# SprinklerPi.net
KiCad netlist of a schematic drawn in EAGLE
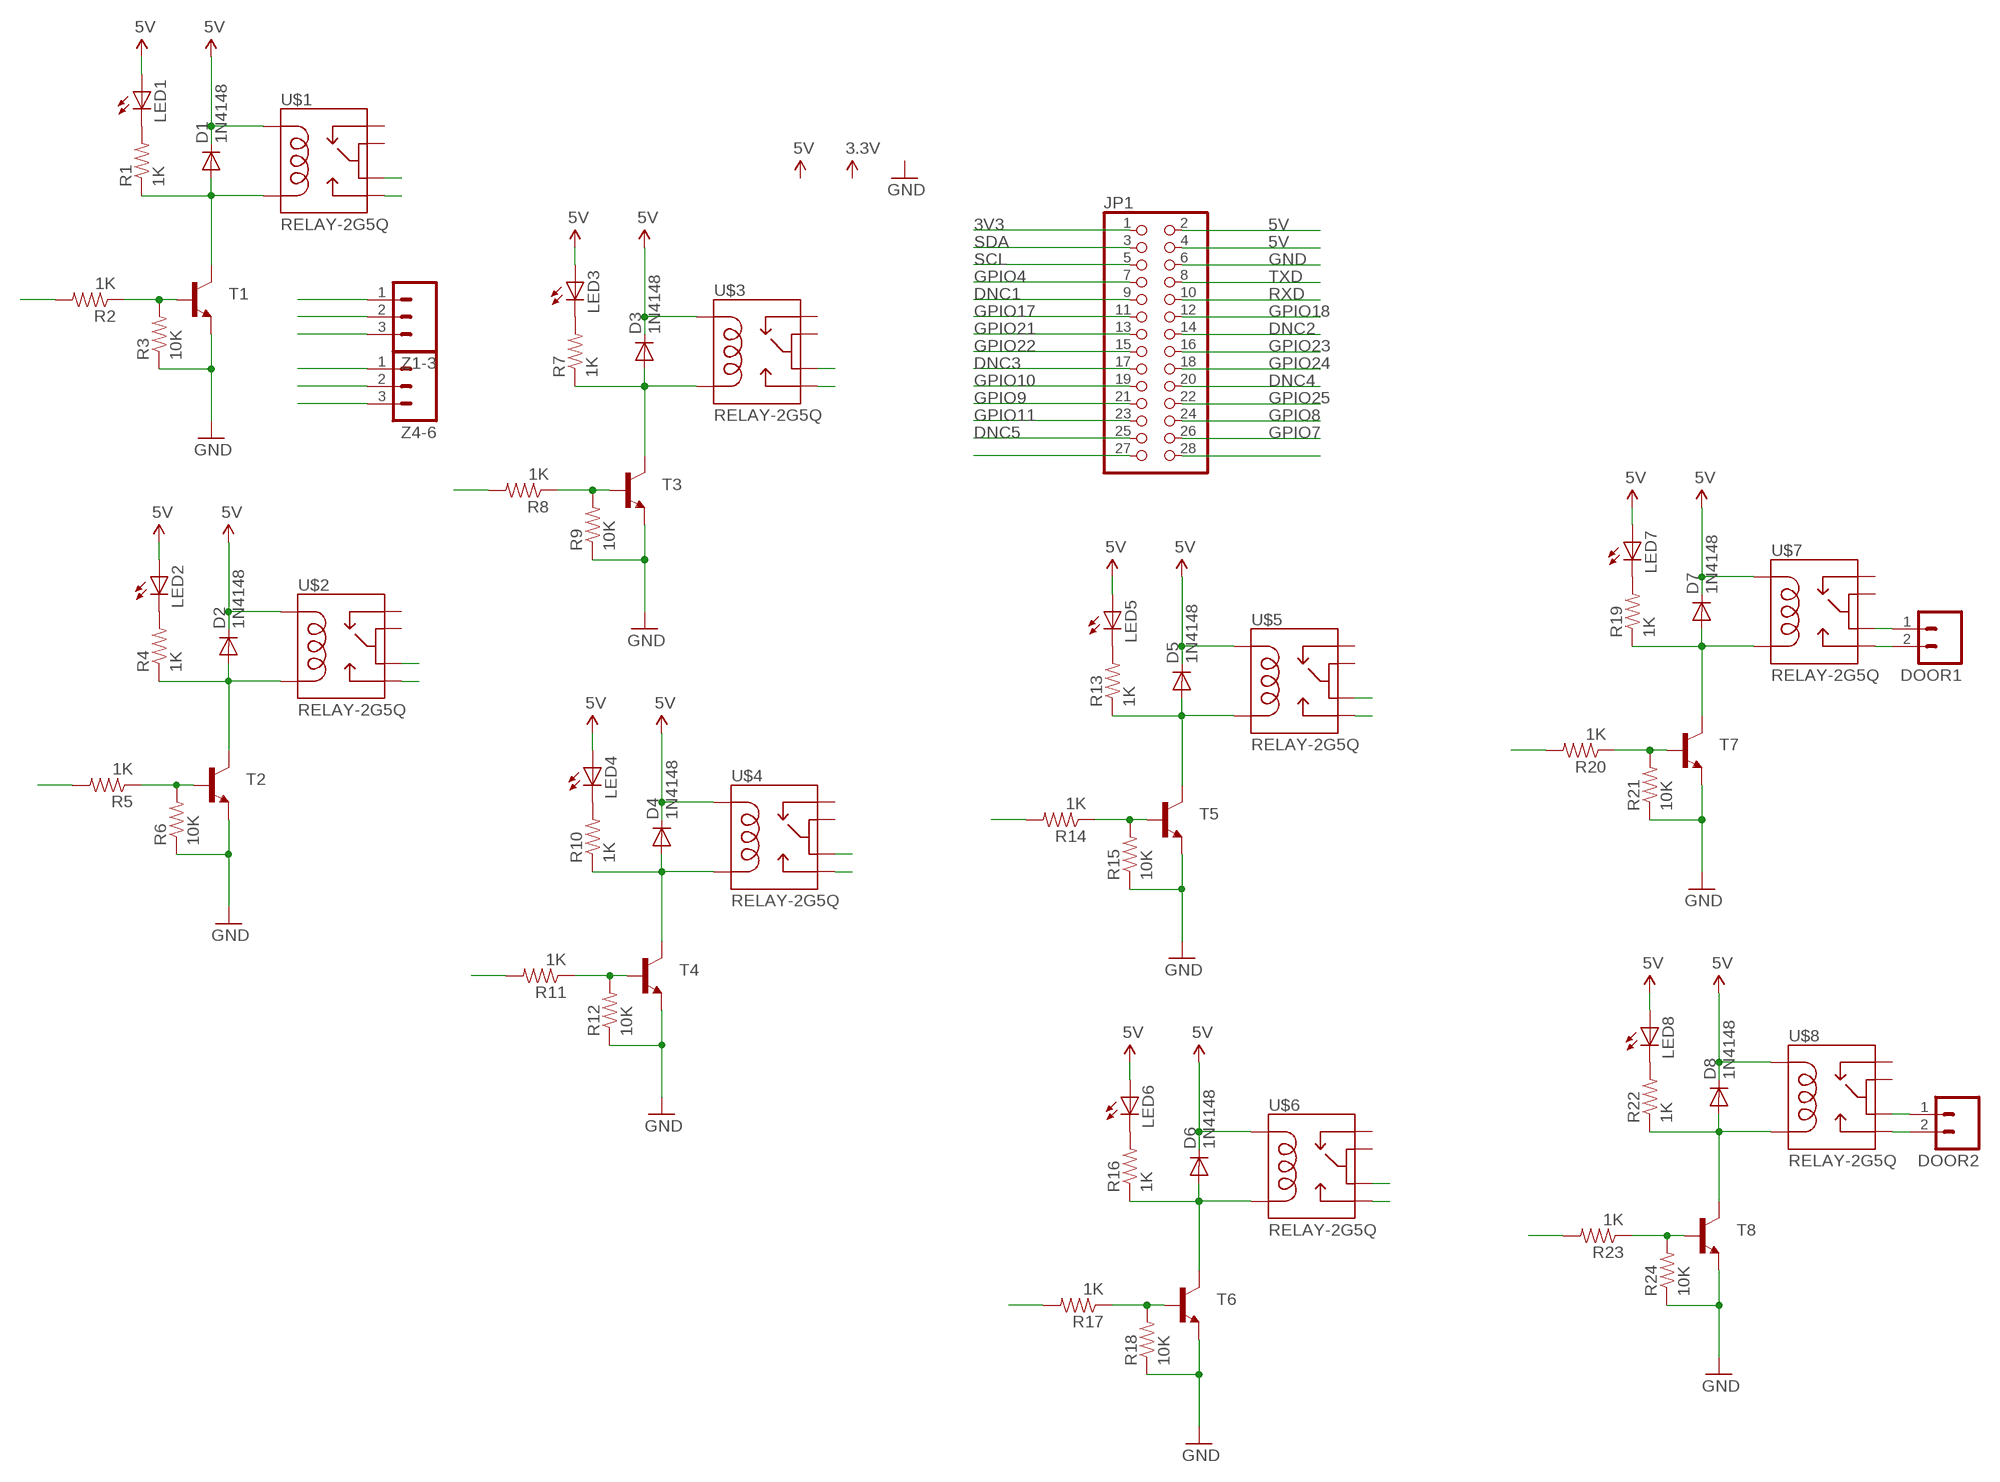
[diagram p0: schematic, sheet 1]

(export (version "E")
  (design (tool "Eeschema 10.0.6"))
  (components
    (comp (ref "D1")
      (value "1N4148")
      (footprint "eagle-import:DIODE-1N4148")
      (libsource (lib "eagle-import") (part "DIODE1N4148"))
    )
    (comp (ref "D2")
      (value "1N4148")
      (footprint "eagle-import:DIODE-1N4148")
      (libsource (lib "eagle-import") (part "DIODE1N4148"))
    )
    (comp (ref "D3")
      (value "1N4148")
      (footprint "eagle-import:DIODE-1N4148")
      (libsource (lib "eagle-import") (part "DIODE1N4148"))
    )
    (comp (ref "D4")
      (value "1N4148")
      (footprint "eagle-import:DIODE-1N4148")
      (libsource (lib "eagle-import") (part "DIODE1N4148"))
    )
    (comp (ref "D5")
      (value "1N4148")
      (footprint "eagle-import:DIODE-1N4148")
      (libsource (lib "eagle-import") (part "DIODE1N4148"))
    )
    (comp (ref "D6")
      (value "1N4148")
      (footprint "eagle-import:DIODE-1N4148")
      (libsource (lib "eagle-import") (part "DIODE1N4148"))
    )
    (comp (ref "D7")
      (value "1N4148")
      (footprint "eagle-import:DIODE-1N4148")
      (libsource (lib "eagle-import") (part "DIODE1N4148"))
    )
    (comp (ref "D8")
      (value "1N4148")
      (footprint "eagle-import:DIODE-1N4148")
      (libsource (lib "eagle-import") (part "DIODE1N4148"))
    )
    (comp (ref "DOOR1")
      (value "M023.5MM")
      (footprint "eagle-import:SCREWTERMINAL-3.5MM-2")
      (libsource (lib "eagle-import") (part "M023.5MM"))
    )
    (comp (ref "DOOR2")
      (value "M023.5MM")
      (footprint "eagle-import:SCREWTERMINAL-3.5MM-2")
      (libsource (lib "eagle-import") (part "M023.5MM"))
    )
    (comp (ref "JP1")
      (value "PINHD-2X14-CB")
      (footprint "eagle-import:2X14-CLEANBIG")
      (libsource (lib "eagle-import") (part "PINHD-2X14-CB"))
    )
    (comp (ref "LED1")
      (value "LED-RED1206")
      (footprint "eagle-import:LED-1206")
      (libsource (lib "eagle-import") (part "LED-RED1206"))
    )
    (comp (ref "LED2")
      (value "LED-RED1206")
      (footprint "eagle-import:LED-1206")
      (libsource (lib "eagle-import") (part "LED-RED1206"))
    )
    (comp (ref "LED3")
      (value "LED-RED1206")
      (footprint "eagle-import:LED-1206")
      (libsource (lib "eagle-import") (part "LED-RED1206"))
    )
    (comp (ref "LED4")
      (value "LED-RED1206")
      (footprint "eagle-import:LED-1206")
      (libsource (lib "eagle-import") (part "LED-RED1206"))
    )
    (comp (ref "LED5")
      (value "LED-RED1206")
      (footprint "eagle-import:LED-1206")
      (libsource (lib "eagle-import") (part "LED-RED1206"))
    )
    (comp (ref "LED6")
      (value "LED-RED1206")
      (footprint "eagle-import:LED-1206")
      (libsource (lib "eagle-import") (part "LED-RED1206"))
    )
    (comp (ref "LED7")
      (value "LED-RED1206")
      (footprint "eagle-import:LED-1206")
      (libsource (lib "eagle-import") (part "LED-RED1206"))
    )
    (comp (ref "LED8")
      (value "LED-RED1206")
      (footprint "eagle-import:LED-1206")
      (libsource (lib "eagle-import") (part "LED-RED1206"))
    )
    (comp (ref "R1")
      (value "1K")
      (footprint "eagle-import:0805")
      (libsource (lib "eagle-import") (part "RESISTOR0805-RES"))
    )
    (comp (ref "R2")
      (value "1K")
      (footprint "eagle-import:0805")
      (libsource (lib "eagle-import") (part "RESISTOR0805-RES"))
    )
    (comp (ref "R3")
      (value "10K")
      (footprint "eagle-import:0805")
      (libsource (lib "eagle-import") (part "RESISTOR0805-RES"))
    )
    (comp (ref "R4")
      (value "1K")
      (footprint "eagle-import:0805")
      (libsource (lib "eagle-import") (part "RESISTOR0805-RES"))
    )
    (comp (ref "R5")
      (value "1K")
      (footprint "eagle-import:0805")
      (libsource (lib "eagle-import") (part "RESISTOR0805-RES"))
    )
    (comp (ref "R6")
      (value "10K")
      (footprint "eagle-import:0805")
      (libsource (lib "eagle-import") (part "RESISTOR0805-RES"))
    )
    (comp (ref "R7")
      (value "1K")
      (footprint "eagle-import:0805")
      (libsource (lib "eagle-import") (part "RESISTOR0805-RES"))
    )
    (comp (ref "R8")
      (value "1K")
      (footprint "eagle-import:0805")
      (libsource (lib "eagle-import") (part "RESISTOR0805-RES"))
    )
    (comp (ref "R9")
      (value "10K")
      (footprint "eagle-import:0805")
      (libsource (lib "eagle-import") (part "RESISTOR0805-RES"))
    )
    (comp (ref "R10")
      (value "1K")
      (footprint "eagle-import:0805")
      (libsource (lib "eagle-import") (part "RESISTOR0805-RES"))
    )
    (comp (ref "R11")
      (value "1K")
      (footprint "eagle-import:0805")
      (libsource (lib "eagle-import") (part "RESISTOR0805-RES"))
    )
    (comp (ref "R12")
      (value "10K")
      (footprint "eagle-import:0805")
      (libsource (lib "eagle-import") (part "RESISTOR0805-RES"))
    )
    (comp (ref "R13")
      (value "1K")
      (footprint "eagle-import:0805")
      (libsource (lib "eagle-import") (part "RESISTOR0805-RES"))
    )
    (comp (ref "R14")
      (value "1K")
      (footprint "eagle-import:0805")
      (libsource (lib "eagle-import") (part "RESISTOR0805-RES"))
    )
    (comp (ref "R15")
      (value "10K")
      (footprint "eagle-import:0805")
      (libsource (lib "eagle-import") (part "RESISTOR0805-RES"))
    )
    (comp (ref "R16")
      (value "1K")
      (footprint "eagle-import:0805")
      (libsource (lib "eagle-import") (part "RESISTOR0805-RES"))
    )
    (comp (ref "R17")
      (value "1K")
      (footprint "eagle-import:0805")
      (libsource (lib "eagle-import") (part "RESISTOR0805-RES"))
    )
    (comp (ref "R18")
      (value "10K")
      (footprint "eagle-import:0805")
      (libsource (lib "eagle-import") (part "RESISTOR0805-RES"))
    )
    (comp (ref "R19")
      (value "1K")
      (footprint "eagle-import:0805")
      (libsource (lib "eagle-import") (part "RESISTOR0805-RES"))
    )
    (comp (ref "R20")
      (value "1K")
      (footprint "eagle-import:0805")
      (libsource (lib "eagle-import") (part "RESISTOR0805-RES"))
    )
    (comp (ref "R21")
      (value "10K")
      (footprint "eagle-import:0805")
      (libsource (lib "eagle-import") (part "RESISTOR0805-RES"))
    )
    (comp (ref "R22")
      (value "1K")
      (footprint "eagle-import:0805")
      (libsource (lib "eagle-import") (part "RESISTOR0805-RES"))
    )
    (comp (ref "R23")
      (value "1K")
      (footprint "eagle-import:0805")
      (libsource (lib "eagle-import") (part "RESISTOR0805-RES"))
    )
    (comp (ref "R24")
      (value "10K")
      (footprint "eagle-import:0805")
      (libsource (lib "eagle-import") (part "RESISTOR0805-RES"))
    )
    (comp (ref "T1")
      (value "TRANSISTOR_NPNSOT23")
      (footprint "eagle-import:SOT23")
      (libsource (lib "eagle-import") (part "TRANSISTOR_NPNSOT23"))
    )
    (comp (ref "T2")
      (value "TRANSISTOR_NPNSOT23")
      (footprint "eagle-import:SOT23")
      (libsource (lib "eagle-import") (part "TRANSISTOR_NPNSOT23"))
    )
    (comp (ref "T3")
      (value "TRANSISTOR_NPNSOT23")
      (footprint "eagle-import:SOT23")
      (libsource (lib "eagle-import") (part "TRANSISTOR_NPNSOT23"))
    )
    (comp (ref "T4")
      (value "TRANSISTOR_NPNSOT23")
      (footprint "eagle-import:SOT23")
      (libsource (lib "eagle-import") (part "TRANSISTOR_NPNSOT23"))
    )
    (comp (ref "T5")
      (value "TRANSISTOR_NPNSOT23")
      (footprint "eagle-import:SOT23")
      (libsource (lib "eagle-import") (part "TRANSISTOR_NPNSOT23"))
    )
    (comp (ref "T6")
      (value "TRANSISTOR_NPNSOT23")
      (footprint "eagle-import:SOT23")
      (libsource (lib "eagle-import") (part "TRANSISTOR_NPNSOT23"))
    )
    (comp (ref "T7")
      (value "TRANSISTOR_NPNSOT23")
      (footprint "eagle-import:SOT23")
      (libsource (lib "eagle-import") (part "TRANSISTOR_NPNSOT23"))
    )
    (comp (ref "T8")
      (value "TRANSISTOR_NPNSOT23")
      (footprint "eagle-import:SOT23")
      (libsource (lib "eagle-import") (part "TRANSISTOR_NPNSOT23"))
    )
    (comp (ref "U$1")
      (value "RELAY-2G5Q")
      (footprint "eagle-import:RELAY-G5V")
      (libsource (lib "eagle-import") (part "RELAY-2G5Q"))
    )
    (comp (ref "U$2")
      (value "RELAY-2G5Q")
      (footprint "eagle-import:RELAY-G5V")
      (libsource (lib "eagle-import") (part "RELAY-2G5Q"))
    )
    (comp (ref "U$3")
      (value "RELAY-2G5Q")
      (footprint "eagle-import:RELAY-G5V")
      (libsource (lib "eagle-import") (part "RELAY-2G5Q"))
    )
    (comp (ref "U$4")
      (value "RELAY-2G5Q")
      (footprint "eagle-import:RELAY-G5V")
      (libsource (lib "eagle-import") (part "RELAY-2G5Q"))
    )
    (comp (ref "U$5")
      (value "RELAY-2G5Q")
      (footprint "eagle-import:RELAY-G5V")
      (libsource (lib "eagle-import") (part "RELAY-2G5Q"))
    )
    (comp (ref "U$6")
      (value "RELAY-2G5Q")
      (footprint "eagle-import:RELAY-G5V")
      (libsource (lib "eagle-import") (part "RELAY-2G5Q"))
    )
    (comp (ref "U$7")
      (value "RELAY-2G5Q")
      (footprint "eagle-import:RELAY-G5V")
      (libsource (lib "eagle-import") (part "RELAY-2G5Q"))
    )
    (comp (ref "U$8")
      (value "RELAY-2G5Q")
      (footprint "eagle-import:RELAY-G5V")
      (libsource (lib "eagle-import") (part "RELAY-2G5Q"))
    )
    (comp (ref "Z1-3")
      (value "M03SCREW")
      (footprint "eagle-import:SCREWTERMINAL-3.5MM-3")
      (libsource (lib "eagle-import") (part "M03SCREW"))
    )
    (comp (ref "Z4-6")
      (value "M03SCREW")
      (footprint "eagle-import:SCREWTERMINAL-3.5MM-3")
      (libsource (lib "eagle-import") (part "M03SCREW"))
    )
  )
  (nets
    (net (code "1") (name "/3V3") (class "Default")
      (node (ref "JP1") (pin "1") (pinfunction "1_1") (pintype "passive"))
    )
    (net (code "2") (name "/DNC1") (class "Default")
      (node (ref "JP1") (pin "9") (pinfunction "9_9") (pintype "passive"))
    )
    (net (code "3") (name "/DNC2") (class "Default")
      (node (ref "JP1") (pin "14") (pinfunction "14_14") (pintype "passive"))
    )
    (net (code "4") (name "/DNC3") (class "Default")
      (node (ref "JP1") (pin "17") (pinfunction "17_17") (pintype "passive"))
    )
    (net (code "5") (name "/DNC4") (class "Default")
      (node (ref "JP1") (pin "20") (pinfunction "20_20") (pintype "passive"))
    )
    (net (code "6") (name "/DNC5") (class "Default")
      (node (ref "JP1") (pin "25") (pinfunction "25_25") (pintype "passive"))
    )
    (net (code "7") (name "/GPIO4") (class "Default")
      (node (ref "JP1") (pin "7") (pinfunction "7_7") (pintype "passive"))
    )
    (net (code "8") (name "/GPIO7") (class "Default")
      (node (ref "JP1") (pin "26") (pinfunction "26_26") (pintype "passive"))
    )
    (net (code "9") (name "/GPIO8") (class "Default")
      (node (ref "JP1") (pin "24") (pinfunction "24_24") (pintype "passive"))
    )
    (net (code "10") (name "/GPIO9") (class "Default")
      (node (ref "JP1") (pin "21") (pinfunction "21_21") (pintype "passive"))
    )
    (net (code "11") (name "/GPIO10") (class "Default")
      (node (ref "JP1") (pin "19") (pinfunction "19_19") (pintype "passive"))
    )
    (net (code "12") (name "/GPIO11") (class "Default")
      (node (ref "JP1") (pin "23") (pinfunction "23_23") (pintype "passive"))
    )
    (net (code "13") (name "/GPIO17") (class "Default")
      (node (ref "JP1") (pin "11") (pinfunction "11_11") (pintype "passive"))
    )
    (net (code "14") (name "/GPIO18") (class "Default")
      (node (ref "JP1") (pin "12") (pinfunction "12_12") (pintype "passive"))
    )
    (net (code "15") (name "/GPIO21") (class "Default")
      (node (ref "JP1") (pin "13") (pinfunction "13_13") (pintype "passive"))
    )
    (net (code "16") (name "/GPIO22") (class "Default")
      (node (ref "JP1") (pin "15") (pinfunction "15_15") (pintype "passive"))
    )
    (net (code "17") (name "/GPIO23") (class "Default")
      (node (ref "JP1") (pin "16") (pinfunction "16_16") (pintype "passive"))
    )
    (net (code "18") (name "/GPIO24") (class "Default")
      (node (ref "JP1") (pin "18") (pinfunction "18_18") (pintype "passive"))
    )
    (net (code "19") (name "/GPIO25") (class "Default")
      (node (ref "JP1") (pin "22") (pinfunction "22_22") (pintype "passive"))
    )
    (net (code "20") (name "/RXD") (class "Default")
      (node (ref "JP1") (pin "10") (pinfunction "10_10") (pintype "passive"))
    )
    (net (code "21") (name "/SCL") (class "Default")
      (node (ref "JP1") (pin "5") (pinfunction "5_5") (pintype "passive"))
    )
    (net (code "22") (name "/SDA") (class "Default")
      (node (ref "JP1") (pin "3") (pinfunction "3_3") (pintype "passive"))
    )
    (net (code "23") (name "/TXD") (class "Default")
      (node (ref "JP1") (pin "8") (pinfunction "8_8") (pintype "passive"))
    )
    (net (code "24") (name "/Z1") (class "Default")
      (node (ref "U$1") (pin "10") (pinfunction "10_10") (pintype "bidirectional"))
      (node (ref "Z1-3") (pin "1") (pinfunction "1_1") (pintype "passive"))
    )
    (net (code "25") (name "/Z2") (class "Default")
      (node (ref "U$2") (pin "10") (pinfunction "10_10") (pintype "bidirectional"))
      (node (ref "Z1-3") (pin "2") (pinfunction "2_2") (pintype "passive"))
    )
    (net (code "26") (name "/Z3") (class "Default")
      (node (ref "U$3") (pin "10") (pinfunction "10_10") (pintype "bidirectional"))
      (node (ref "Z1-3") (pin "3") (pinfunction "3_3") (pintype "passive"))
    )
    (net (code "27") (name "/Z4") (class "Default")
      (node (ref "U$4") (pin "10") (pinfunction "10_10") (pintype "bidirectional"))
      (node (ref "Z4-6") (pin "1") (pinfunction "1_1") (pintype "passive"))
    )
    (net (code "28") (name "/Z5") (class "Default")
      (node (ref "U$5") (pin "10") (pinfunction "10_10") (pintype "bidirectional"))
      (node (ref "Z4-6") (pin "2") (pinfunction "2_2") (pintype "passive"))
    )
    (net (code "29") (name "/Z6") (class "Default")
      (node (ref "U$6") (pin "10") (pinfunction "10_10") (pintype "bidirectional"))
      (node (ref "Z4-6") (pin "3") (pinfunction "3_3") (pintype "passive"))
    )
    (net (code "31") (name "5V") (class "Default")
      (node (ref "D1") (pin "C") (pinfunction "C_C") (pintype "passive"))
      (node (ref "D2") (pin "C") (pinfunction "C_C") (pintype "passive"))
      (node (ref "D3") (pin "C") (pinfunction "C_C") (pintype "passive"))
      (node (ref "D4") (pin "C") (pinfunction "C_C") (pintype "passive"))
      (node (ref "D5") (pin "C") (pinfunction "C_C") (pintype "passive"))
      (node (ref "D6") (pin "C") (pinfunction "C_C") (pintype "passive"))
      (node (ref "D7") (pin "C") (pinfunction "C_C") (pintype "passive"))
      (node (ref "D8") (pin "C") (pinfunction "C_C") (pintype "passive"))
      (node (ref "JP1") (pin "2") (pinfunction "2_2") (pintype "passive"))
      (node (ref "JP1") (pin "4") (pinfunction "4_4") (pintype "passive"))
      (node (ref "LED1") (pin "A") (pinfunction "A_A") (pintype "passive"))
      (node (ref "LED2") (pin "A") (pinfunction "A_A") (pintype "passive"))
      (node (ref "LED3") (pin "A") (pinfunction "A_A") (pintype "passive"))
      (node (ref "LED4") (pin "A") (pinfunction "A_A") (pintype "passive"))
      (node (ref "LED5") (pin "A") (pinfunction "A_A") (pintype "passive"))
      (node (ref "LED6") (pin "A") (pinfunction "A_A") (pintype "passive"))
      (node (ref "LED7") (pin "A") (pinfunction "A_A") (pintype "passive"))
      (node (ref "LED8") (pin "A") (pinfunction "A_A") (pintype "passive"))
      (node (ref "U$1") (pin "2") (pinfunction "2_2") (pintype "bidirectional"))
      (node (ref "U$2") (pin "2") (pinfunction "2_2") (pintype "bidirectional"))
      (node (ref "U$3") (pin "2") (pinfunction "2_2") (pintype "bidirectional"))
      (node (ref "U$4") (pin "2") (pinfunction "2_2") (pintype "bidirectional"))
      (node (ref "U$5") (pin "2") (pinfunction "2_2") (pintype "bidirectional"))
      (node (ref "U$6") (pin "2") (pinfunction "2_2") (pintype "bidirectional"))
      (node (ref "U$7") (pin "2") (pinfunction "2_2") (pintype "bidirectional"))
      (node (ref "U$8") (pin "2") (pinfunction "2_2") (pintype "bidirectional"))
    )
    (net (code "32") (name "GND") (class "Default")
      (node (ref "JP1") (pin "6") (pinfunction "6_6") (pintype "passive"))
      (node (ref "R12") (pin "1") (pinfunction "1_1") (pintype "passive"))
      (node (ref "R15") (pin "1") (pinfunction "1_1") (pintype "passive"))
      (node (ref "R18") (pin "1") (pinfunction "1_1") (pintype "passive"))
      (node (ref "R21") (pin "1") (pinfunction "1_1") (pintype "passive"))
      (node (ref "R24") (pin "1") (pinfunction "1_1") (pintype "passive"))
      (node (ref "R3") (pin "1") (pinfunction "1_1") (pintype "passive"))
      (node (ref "R6") (pin "1") (pinfunction "1_1") (pintype "passive"))
      (node (ref "R9") (pin "1") (pinfunction "1_1") (pintype "passive"))
      (node (ref "T1") (pin "2") (pinfunction "E_2") (pintype "passive"))
      (node (ref "T2") (pin "2") (pinfunction "E_2") (pintype "passive"))
      (node (ref "T3") (pin "2") (pinfunction "E_2") (pintype "passive"))
      (node (ref "T4") (pin "2") (pinfunction "E_2") (pintype "passive"))
      (node (ref "T5") (pin "2") (pinfunction "E_2") (pintype "passive"))
      (node (ref "T6") (pin "2") (pinfunction "E_2") (pintype "passive"))
      (node (ref "T7") (pin "2") (pinfunction "E_2") (pintype "passive"))
      (node (ref "T8") (pin "2") (pinfunction "E_2") (pintype "passive"))
    )
    (net (code "33") (name "Net-(DOOR1-Pad1)") (class "Default")
      (node (ref "DOOR1") (pin "1") (pinfunction "1_1") (pintype "passive"))
      (node (ref "U$7") (pin "6") (pinfunction "6_6") (pintype "bidirectional"))
    )
    (net (code "34") (name "Net-(DOOR1-Pad2)") (class "Default")
      (node (ref "DOOR1") (pin "2") (pinfunction "2_2") (pintype "passive"))
      (node (ref "U$7") (pin "10") (pinfunction "10_10") (pintype "bidirectional"))
    )
    (net (code "35") (name "Net-(DOOR2-Pad1)") (class "Default")
      (node (ref "DOOR2") (pin "1") (pinfunction "1_1") (pintype "passive"))
      (node (ref "U$8") (pin "6") (pinfunction "6_6") (pintype "bidirectional"))
    )
    (net (code "36") (name "Net-(DOOR2-Pad2)") (class "Default")
      (node (ref "DOOR2") (pin "2") (pinfunction "2_2") (pintype "passive"))
      (node (ref "U$8") (pin "10") (pinfunction "10_10") (pintype "bidirectional"))
    )
    (net (code "37") (name "Net-(LED1-PadC)") (class "Default")
      (node (ref "LED1") (pin "C") (pinfunction "C_C") (pintype "passive"))
      (node (ref "R1") (pin "2") (pinfunction "2_2") (pintype "passive"))
    )
    (net (code "38") (name "Net-(LED2-PadC)") (class "Default")
      (node (ref "LED2") (pin "C") (pinfunction "C_C") (pintype "passive"))
      (node (ref "R4") (pin "2") (pinfunction "2_2") (pintype "passive"))
    )
    (net (code "39") (name "Net-(LED3-PadC)") (class "Default")
      (node (ref "LED3") (pin "C") (pinfunction "C_C") (pintype "passive"))
      (node (ref "R7") (pin "2") (pinfunction "2_2") (pintype "passive"))
    )
    (net (code "40") (name "Net-(LED4-PadC)") (class "Default")
      (node (ref "LED4") (pin "C") (pinfunction "C_C") (pintype "passive"))
      (node (ref "R10") (pin "2") (pinfunction "2_2") (pintype "passive"))
    )
    (net (code "41") (name "Net-(LED5-PadC)") (class "Default")
      (node (ref "LED5") (pin "C") (pinfunction "C_C") (pintype "passive"))
      (node (ref "R13") (pin "2") (pinfunction "2_2") (pintype "passive"))
    )
    (net (code "42") (name "Net-(LED6-PadC)") (class "Default")
      (node (ref "LED6") (pin "C") (pinfunction "C_C") (pintype "passive"))
      (node (ref "R16") (pin "2") (pinfunction "2_2") (pintype "passive"))
    )
    (net (code "43") (name "Net-(LED7-PadC)") (class "Default")
      (node (ref "LED7") (pin "C") (pinfunction "C_C") (pintype "passive"))
      (node (ref "R19") (pin "2") (pinfunction "2_2") (pintype "passive"))
    )
    (net (code "44") (name "Net-(LED8-PadC)") (class "Default")
      (node (ref "LED8") (pin "C") (pinfunction "C_C") (pintype "passive"))
      (node (ref "R22") (pin "2") (pinfunction "2_2") (pintype "passive"))
    )
    (net (code "45") (name "Net-(T1-B)") (class "Default")
      (node (ref "R2") (pin "1") (pinfunction "1_1") (pintype "passive"))
      (node (ref "R3") (pin "2") (pinfunction "2_2") (pintype "passive"))
      (node (ref "T1") (pin "1") (pinfunction "B_1") (pintype "passive"))
    )
    (net (code "46") (name "Net-(T1-C)") (class "Default")
      (node (ref "D1") (pin "A") (pinfunction "A_A") (pintype "passive"))
      (node (ref "R1") (pin "1") (pinfunction "1_1") (pintype "passive"))
      (node (ref "T1") (pin "3") (pinfunction "C_3") (pintype "passive"))
      (node (ref "U$1") (pin "9") (pinfunction "9_9") (pintype "bidirectional"))
    )
    (net (code "47") (name "Net-(T2-B)") (class "Default")
      (node (ref "R5") (pin "1") (pinfunction "1_1") (pintype "passive"))
      (node (ref "R6") (pin "2") (pinfunction "2_2") (pintype "passive"))
      (node (ref "T2") (pin "1") (pinfunction "B_1") (pintype "passive"))
    )
    (net (code "48") (name "Net-(T2-C)") (class "Default")
      (node (ref "D2") (pin "A") (pinfunction "A_A") (pintype "passive"))
      (node (ref "R4") (pin "1") (pinfunction "1_1") (pintype "passive"))
      (node (ref "T2") (pin "3") (pinfunction "C_3") (pintype "passive"))
      (node (ref "U$2") (pin "9") (pinfunction "9_9") (pintype "bidirectional"))
    )
    (net (code "49") (name "Net-(T3-B)") (class "Default")
      (node (ref "R8") (pin "1") (pinfunction "1_1") (pintype "passive"))
      (node (ref "R9") (pin "2") (pinfunction "2_2") (pintype "passive"))
      (node (ref "T3") (pin "1") (pinfunction "B_1") (pintype "passive"))
    )
    (net (code "50") (name "Net-(T3-C)") (class "Default")
      (node (ref "D3") (pin "A") (pinfunction "A_A") (pintype "passive"))
      (node (ref "R7") (pin "1") (pinfunction "1_1") (pintype "passive"))
      (node (ref "T3") (pin "3") (pinfunction "C_3") (pintype "passive"))
      (node (ref "U$3") (pin "9") (pinfunction "9_9") (pintype "bidirectional"))
    )
    (net (code "51") (name "Net-(T4-B)") (class "Default")
      (node (ref "R11") (pin "1") (pinfunction "1_1") (pintype "passive"))
      (node (ref "R12") (pin "2") (pinfunction "2_2") (pintype "passive"))
      (node (ref "T4") (pin "1") (pinfunction "B_1") (pintype "passive"))
    )
    (net (code "52") (name "Net-(T4-C)") (class "Default")
      (node (ref "D4") (pin "A") (pinfunction "A_A") (pintype "passive"))
      (node (ref "R10") (pin "1") (pinfunction "1_1") (pintype "passive"))
      (node (ref "T4") (pin "3") (pinfunction "C_3") (pintype "passive"))
      (node (ref "U$4") (pin "9") (pinfunction "9_9") (pintype "bidirectional"))
    )
    (net (code "53") (name "Net-(T5-B)") (class "Default")
      (node (ref "R14") (pin "1") (pinfunction "1_1") (pintype "passive"))
      (node (ref "R15") (pin "2") (pinfunction "2_2") (pintype "passive"))
      (node (ref "T5") (pin "1") (pinfunction "B_1") (pintype "passive"))
    )
    (net (code "54") (name "Net-(T5-C)") (class "Default")
      (node (ref "D5") (pin "A") (pinfunction "A_A") (pintype "passive"))
      (node (ref "R13") (pin "1") (pinfunction "1_1") (pintype "passive"))
      (node (ref "T5") (pin "3") (pinfunction "C_3") (pintype "passive"))
      (node (ref "U$5") (pin "9") (pinfunction "9_9") (pintype "bidirectional"))
    )
    (net (code "55") (name "Net-(T6-B)") (class "Default")
      (node (ref "R17") (pin "1") (pinfunction "1_1") (pintype "passive"))
      (node (ref "R18") (pin "2") (pinfunction "2_2") (pintype "passive"))
      (node (ref "T6") (pin "1") (pinfunction "B_1") (pintype "passive"))
    )
    (net (code "56") (name "Net-(T6-C)") (class "Default")
      (node (ref "D6") (pin "A") (pinfunction "A_A") (pintype "passive"))
      (node (ref "R16") (pin "1") (pinfunction "1_1") (pintype "passive"))
      (node (ref "T6") (pin "3") (pinfunction "C_3") (pintype "passive"))
      (node (ref "U$6") (pin "9") (pinfunction "9_9") (pintype "bidirectional"))
    )
    (net (code "57") (name "Net-(T7-B)") (class "Default")
      (node (ref "R20") (pin "1") (pinfunction "1_1") (pintype "passive"))
      (node (ref "R21") (pin "2") (pinfunction "2_2") (pintype "passive"))
      (node (ref "T7") (pin "1") (pinfunction "B_1") (pintype "passive"))
    )
    (net (code "58") (name "Net-(T7-C)") (class "Default")
      (node (ref "D7") (pin "A") (pinfunction "A_A") (pintype "passive"))
      (node (ref "R19") (pin "1") (pinfunction "1_1") (pintype "passive"))
      (node (ref "T7") (pin "3") (pinfunction "C_3") (pintype "passive"))
      (node (ref "U$7") (pin "9") (pinfunction "9_9") (pintype "bidirectional"))
    )
    (net (code "59") (name "Net-(T8-B)") (class "Default")
      (node (ref "R23") (pin "1") (pinfunction "1_1") (pintype "passive"))
      (node (ref "R24") (pin "2") (pinfunction "2_2") (pintype "passive"))
      (node (ref "T8") (pin "1") (pinfunction "B_1") (pintype "passive"))
    )
    (net (code "60") (name "Net-(T8-C)") (class "Default")
      (node (ref "D8") (pin "A") (pinfunction "A_A") (pintype "passive"))
      (node (ref "R22") (pin "1") (pinfunction "1_1") (pintype "passive"))
      (node (ref "T8") (pin "3") (pinfunction "C_3") (pintype "passive"))
      (node (ref "U$8") (pin "9") (pinfunction "9_9") (pintype "bidirectional"))
    )
    (net (code "61") (name "unconnected-(JP1-Pad27)") (class "Default")
      (node (ref "JP1") (pin "27") (pinfunction "27_27") (pintype "passive"))
    )
    (net (code "62") (name "unconnected-(JP1-Pad28)") (class "Default")
      (node (ref "JP1") (pin "28") (pinfunction "28_28") (pintype "passive"))
    )
    (net (code "63") (name "unconnected-(R2-Pad2)") (class "Default")
      (node (ref "R2") (pin "2") (pinfunction "2_2") (pintype "passive"))
    )
    (net (code "64") (name "unconnected-(R5-Pad2)") (class "Default")
      (node (ref "R5") (pin "2") (pinfunction "2_2") (pintype "passive"))
    )
    (net (code "65") (name "unconnected-(R8-Pad2)") (class "Default")
      (node (ref "R8") (pin "2") (pinfunction "2_2") (pintype "passive"))
    )
    (net (code "66") (name "unconnected-(R11-Pad2)") (class "Default")
      (node (ref "R11") (pin "2") (pinfunction "2_2") (pintype "passive"))
    )
    (net (code "67") (name "unconnected-(R14-Pad2)") (class "Default")
      (node (ref "R14") (pin "2") (pinfunction "2_2") (pintype "passive"))
    )
    (net (code "68") (name "unconnected-(R17-Pad2)") (class "Default")
      (node (ref "R17") (pin "2") (pinfunction "2_2") (pintype "passive"))
    )
    (net (code "69") (name "unconnected-(R20-Pad2)") (class "Default")
      (node (ref "R20") (pin "2") (pinfunction "2_2") (pintype "passive"))
    )
    (net (code "70") (name "unconnected-(R23-Pad2)") (class "Default")
      (node (ref "R23") (pin "2") (pinfunction "2_2") (pintype "passive"))
    )
    (net (code "71") (name "unconnected-(U$1-Pad1)") (class "Default")
      (node (ref "U$1") (pin "1") (pinfunction "1_1") (pintype "bidirectional"))
    )
    (net (code "72") (name "unconnected-(U$1-Pad5)") (class "Default")
      (node (ref "U$1") (pin "5") (pinfunction "5_5") (pintype "bidirectional"))
    )
    (net (code "73") (name "unconnected-(U$1-Pad6)") (class "Default")
      (node (ref "U$1") (pin "6") (pinfunction "6_6") (pintype "bidirectional"))
    )
    (net (code "74") (name "unconnected-(U$2-Pad1)") (class "Default")
      (node (ref "U$2") (pin "1") (pinfunction "1_1") (pintype "bidirectional"))
    )
    (net (code "75") (name "unconnected-(U$2-Pad5)") (class "Default")
      (node (ref "U$2") (pin "5") (pinfunction "5_5") (pintype "bidirectional"))
    )
    (net (code "76") (name "unconnected-(U$2-Pad6)") (class "Default")
      (node (ref "U$2") (pin "6") (pinfunction "6_6") (pintype "bidirectional"))
    )
    (net (code "77") (name "unconnected-(U$3-Pad1)") (class "Default")
      (node (ref "U$3") (pin "1") (pinfunction "1_1") (pintype "bidirectional"))
    )
    (net (code "78") (name "unconnected-(U$3-Pad5)") (class "Default")
      (node (ref "U$3") (pin "5") (pinfunction "5_5") (pintype "bidirectional"))
    )
    (net (code "79") (name "unconnected-(U$3-Pad6)") (class "Default")
      (node (ref "U$3") (pin "6") (pinfunction "6_6") (pintype "bidirectional"))
    )
    (net (code "80") (name "unconnected-(U$4-Pad1)") (class "Default")
      (node (ref "U$4") (pin "1") (pinfunction "1_1") (pintype "bidirectional"))
    )
    (net (code "81") (name "unconnected-(U$4-Pad5)") (class "Default")
      (node (ref "U$4") (pin "5") (pinfunction "5_5") (pintype "bidirectional"))
    )
    (net (code "82") (name "unconnected-(U$4-Pad6)") (class "Default")
      (node (ref "U$4") (pin "6") (pinfunction "6_6") (pintype "bidirectional"))
    )
    (net (code "83") (name "unconnected-(U$5-Pad1)") (class "Default")
      (node (ref "U$5") (pin "1") (pinfunction "1_1") (pintype "bidirectional"))
    )
    (net (code "84") (name "unconnected-(U$5-Pad5)") (class "Default")
      (node (ref "U$5") (pin "5") (pinfunction "5_5") (pintype "bidirectional"))
    )
    (net (code "85") (name "unconnected-(U$5-Pad6)") (class "Default")
      (node (ref "U$5") (pin "6") (pinfunction "6_6") (pintype "bidirectional"))
    )
    (net (code "86") (name "unconnected-(U$6-Pad1)") (class "Default")
      (node (ref "U$6") (pin "1") (pinfunction "1_1") (pintype "bidirectional"))
    )
    (net (code "87") (name "unconnected-(U$6-Pad5)") (class "Default")
      (node (ref "U$6") (pin "5") (pinfunction "5_5") (pintype "bidirectional"))
    )
    (net (code "88") (name "unconnected-(U$6-Pad6)") (class "Default")
      (node (ref "U$6") (pin "6") (pinfunction "6_6") (pintype "bidirectional"))
    )
    (net (code "89") (name "unconnected-(U$7-Pad1)") (class "Default")
      (node (ref "U$7") (pin "1") (pinfunction "1_1") (pintype "bidirectional"))
    )
    (net (code "90") (name "unconnected-(U$7-Pad5)") (class "Default")
      (node (ref "U$7") (pin "5") (pinfunction "5_5") (pintype "bidirectional"))
    )
    (net (code "91") (name "unconnected-(U$8-Pad1)") (class "Default")
      (node (ref "U$8") (pin "1") (pinfunction "1_1") (pintype "bidirectional"))
    )
    (net (code "92") (name "unconnected-(U$8-Pad5)") (class "Default")
      (node (ref "U$8") (pin "5") (pinfunction "5_5") (pintype "bidirectional"))
    )
  )
)
